# SpeakerStuff.net
KiCad netlist of a schematic drawn in EAGLE
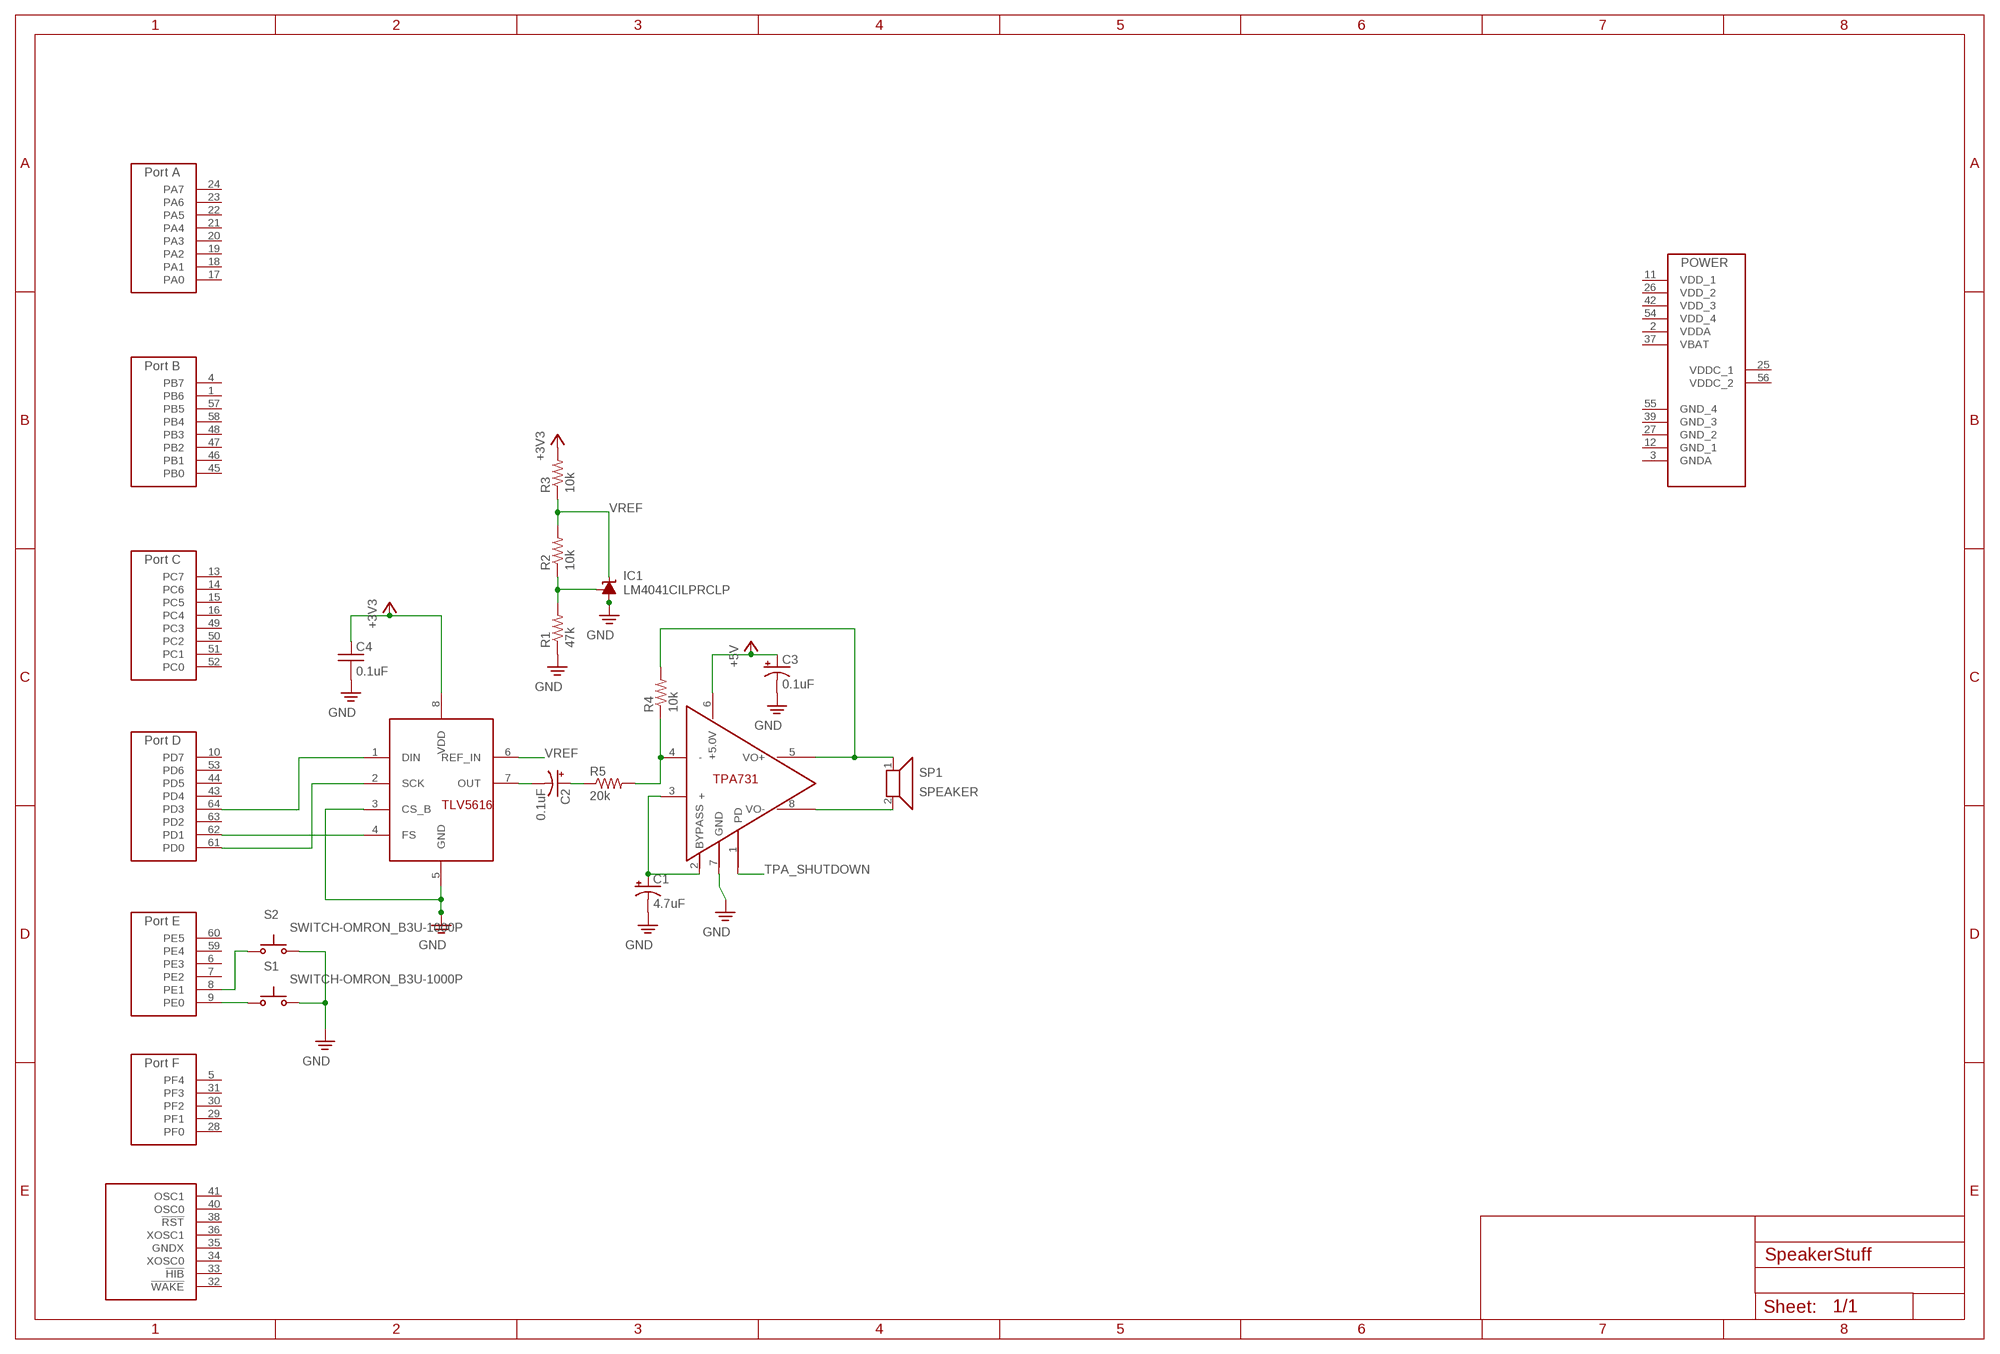
[diagram p0: schematic, sheet 1]

(export (version "E")
  (design (tool "Eeschema 10.0.6"))
  (components
    (comp (ref "C1")
      (value "4.7uF")
      (footprint "eagle-import:CAP200MILPOLARIZED")
      (libsource (lib "eagle-import") (part "CAPACITOR_POLARIZEDE5-6"))
    )
    (comp (ref "C2")
      (value "0.1uF")
      (footprint "eagle-import:CAP200MILPOLARIZED")
      (libsource (lib "eagle-import") (part "CAPACITOR_POLARIZEDE5-6"))
    )
    (comp (ref "C3")
      (value "0.1uF")
      (footprint "eagle-import:CAP200MILPOLARIZED")
      (libsource (lib "eagle-import") (part "CAPACITOR_POLARIZEDE5-6"))
    )
    (comp (ref "C4")
      (value "0.1uF")
      (footprint "eagle-import:C0603K")
      (libsource (lib "eagle-import") (part "CAPACITORC0603K"))
    )
    (comp (ref "IC1")
      (value "LM4041CILPRCLP")
      (footprint "eagle-import:LP_O-PBCY-W3")
      (fields (field (name "MPN") "LM4041CILP"))
      (libsource (lib "eagle-import") (part "LM4041CILPRLPC"))
    )
    (comp (ref "R1")
      (value "47k")
      (footprint "eagle-import:R0603")
      (libsource (lib "eagle-import") (part "RESISTORR0603"))
    )
    (comp (ref "R2")
      (value "10k")
      (footprint "eagle-import:R0603")
      (libsource (lib "eagle-import") (part "RESISTORR0603"))
    )
    (comp (ref "R3")
      (value "10k")
      (footprint "eagle-import:R0603")
      (libsource (lib "eagle-import") (part "RESISTORR0603"))
    )
    (comp (ref "R4")
      (value "10k")
      (footprint "eagle-import:R0603")
      (libsource (lib "eagle-import") (part "RESISTORR0603"))
    )
    (comp (ref "R5")
      (value "20k")
      (footprint "eagle-import:R0603")
      (libsource (lib "eagle-import") (part "RESISTORR0603"))
    )
    (comp (ref "S1")
      (value "SWITCH-OMRON_B3U-1000P")
      (footprint "eagle-import:SWITCH-OMRON_B3U-1000P")
      (libsource (lib "eagle-import") (part "SWITCH-OMRON_B3U-1000P"))
    )
    (comp (ref "S2")
      (value "SWITCH-OMRON_B3U-1000P")
      (footprint "eagle-import:SWITCH-OMRON_B3U-1000P")
      (libsource (lib "eagle-import") (part "SWITCH-OMRON_B3U-1000P"))
    )
    (comp (ref "SP1")
      (value "SPEAKER")
      (footprint "eagle-import:1X02")
      (libsource (lib "eagle-import") (part "SPEAKER"))
    )
    (comp (ref "U$1")
      (value "TM4C123GH6PM")
      (footprint "eagle-import:QFP50P1200X1200X160-64N")
      (libsource (lib "eagle-import") (part "TM4C123GH6PM"))
    )
    (comp (ref "U$2")
      (value "TM4C123GH6PM")
      (footprint "eagle-import:QFP50P1200X1200X160-64N")
      (libsource (lib "eagle-import") (part "TM4C123GH6PM"))
    )
    (comp (ref "U$3")
      (value "TM4C123GH6PM")
      (footprint "eagle-import:QFP50P1200X1200X160-64N")
      (libsource (lib "eagle-import") (part "TM4C123GH6PM"))
    )
    (comp (ref "U$4")
      (value "TM4C123GH6PM")
      (footprint "eagle-import:QFP50P1200X1200X160-64N")
      (libsource (lib "eagle-import") (part "TM4C123GH6PM"))
    )
    (comp (ref "U$5")
      (value "TM4C123GH6PM")
      (footprint "eagle-import:QFP50P1200X1200X160-64N")
      (libsource (lib "eagle-import") (part "TM4C123GH6PM"))
    )
    (comp (ref "U$6")
      (value "TM4C123GH6PM")
      (footprint "eagle-import:QFP50P1200X1200X160-64N")
      (libsource (lib "eagle-import") (part "TM4C123GH6PM"))
    )
    (comp (ref "U$7")
      (value "TM4C123GH6PM")
      (footprint "eagle-import:QFP50P1200X1200X160-64N")
      (libsource (lib "eagle-import") (part "TM4C123GH6PM"))
    )
    (comp (ref "U$8")
      (value "TM4C123GH6PM")
      (footprint "eagle-import:QFP50P1200X1200X160-64N")
      (libsource (lib "eagle-import") (part "TM4C123GH6PM"))
    )
    (comp (ref "U$9")
      (value "TLV5616")
      (footprint "eagle-import:DIL08")
      (libsource (lib "eagle-import") (part "TLV5616"))
    )
    (comp (ref "U$10")
      (value "TPA731")
      (footprint "eagle-import:SO08")
      (libsource (lib "eagle-import") (part "TPA731"))
    )
  )
  (nets
    (net (code "1") (name "+3V3") (class "Default")
      (node (ref "C4") (pin "1") (pinfunction "1_1") (pintype "passive"))
      (node (ref "R3") (pin "2") (pinfunction "2_2") (pintype "passive"))
      (node (ref "U$9") (pin "8") (pinfunction "VDD_8") (pintype "bidirectional"))
    )
    (net (code "2") (name "+5V") (class "Default")
      (node (ref "C3") (pin "+") (pinfunction "+_+") (pintype "passive"))
      (node (ref "U$10") (pin "6") (pinfunction "+5.0V_6") (pintype "bidirectional"))
    )
    (net (code "3") (name "/TPA_SHUTDOWN") (class "Default")
      (node (ref "U$10") (pin "1") (pinfunction "PD_1") (pintype "bidirectional"))
    )
    (net (code "4") (name "/VREF") (class "Default")
      (node (ref "IC1") (pin "2") (pinfunction "C_2") (pintype "passive"))
      (node (ref "R2") (pin "2") (pinfunction "2_2") (pintype "passive"))
      (node (ref "R3") (pin "1") (pinfunction "1_1") (pintype "passive"))
      (node (ref "U$9") (pin "6") (pinfunction "REF_IN_6") (pintype "bidirectional"))
    )
    (net (code "5") (name "GND") (class "Default")
      (node (ref "C1") (pin "-") (pinfunction "-_-") (pintype "passive"))
      (node (ref "C3") (pin "-") (pinfunction "-_-") (pintype "passive"))
      (node (ref "C4") (pin "2") (pinfunction "2_2") (pintype "passive"))
      (node (ref "IC1") (pin "3") (pinfunction "A_3") (pintype "passive"))
      (node (ref "R1") (pin "1") (pinfunction "1_1") (pintype "passive"))
      (node (ref "S1") (pin "2") (pinfunction "S_2") (pintype "passive"))
      (node (ref "S2") (pin "2") (pinfunction "S_2") (pintype "passive"))
      (node (ref "U$10") (pin "7") (pinfunction "GND_7") (pintype "bidirectional"))
      (node (ref "U$9") (pin "3") (pinfunction "CS_B_3") (pintype "bidirectional"))
      (node (ref "U$9") (pin "5") (pinfunction "GND_5") (pintype "bidirectional"))
    )
    (net (code "6") (name "Net-(C2-Pad+)") (class "Default")
      (node (ref "C2") (pin "+") (pinfunction "+_+") (pintype "passive"))
      (node (ref "R5") (pin "1") (pinfunction "1_1") (pintype "passive"))
    )
    (net (code "7") (name "Net-(IC1-FB)") (class "Default")
      (node (ref "IC1") (pin "1") (pinfunction "FB_1") (pintype "passive"))
      (node (ref "R1") (pin "2") (pinfunction "2_2") (pintype "passive"))
      (node (ref "R2") (pin "1") (pinfunction "1_1") (pintype "passive"))
    )
    (net (code "8") (name "Net-(S1-P)") (class "Default")
      (node (ref "S1") (pin "1") (pinfunction "P_1") (pintype "passive"))
      (node (ref "U$6") (pin "9") (pinfunction "PE0_9") (pintype "bidirectional"))
    )
    (net (code "9") (name "Net-(S2-P)") (class "Default")
      (node (ref "S2") (pin "1") (pinfunction "P_1") (pintype "passive"))
      (node (ref "U$6") (pin "8") (pinfunction "PE1_8") (pintype "bidirectional"))
    )
    (net (code "10") (name "Net-(U$5D-PD0)") (class "Default")
      (node (ref "U$5") (pin "61") (pinfunction "PD0_61") (pintype "bidirectional"))
      (node (ref "U$9") (pin "2") (pinfunction "SCK_2") (pintype "bidirectional"))
    )
    (net (code "11") (name "Net-(U$5D-PD1)") (class "Default")
      (node (ref "U$5") (pin "62") (pinfunction "PD1_62") (pintype "bidirectional"))
      (node (ref "U$9") (pin "4") (pinfunction "FS_4") (pintype "bidirectional"))
    )
    (net (code "12") (name "Net-(U$5D-PD3)") (class "Default")
      (node (ref "U$5") (pin "64") (pinfunction "PD3_64") (pintype "bidirectional"))
      (node (ref "U$9") (pin "1") (pinfunction "DIN_1") (pintype "bidirectional"))
    )
    (net (code "13") (name "Net-(U$9-OUT)") (class "Default")
      (node (ref "C2") (pin "-") (pinfunction "-_-") (pintype "passive"))
      (node (ref "U$9") (pin "7") (pinfunction "OUT_7") (pintype "bidirectional"))
    )
    (net (code "14") (name "Net-(U$10-+)") (class "Default")
      (node (ref "C1") (pin "+") (pinfunction "+_+") (pintype "passive"))
      (node (ref "U$10") (pin "2") (pinfunction "BYPASS_2") (pintype "bidirectional"))
      (node (ref "U$10") (pin "3") (pinfunction "+_3") (pintype "bidirectional"))
    )
    (net (code "15") (name "Net-(U$10--)") (class "Default")
      (node (ref "R4") (pin "1") (pinfunction "1_1") (pintype "passive"))
      (node (ref "R5") (pin "2") (pinfunction "2_2") (pintype "passive"))
      (node (ref "U$10") (pin "4") (pinfunction "-_4") (pintype "bidirectional"))
    )
    (net (code "16") (name "Net-(U$10-VO+)") (class "Default")
      (node (ref "R4") (pin "2") (pinfunction "2_2") (pintype "passive"))
      (node (ref "SP1") (pin "1") (pinfunction "1_1") (pintype "passive"))
      (node (ref "U$10") (pin "5") (pinfunction "VO+_5") (pintype "bidirectional"))
    )
    (net (code "17") (name "Net-(U$10-VO-)") (class "Default")
      (node (ref "SP1") (pin "2") (pinfunction "2_2") (pintype "passive"))
      (node (ref "U$10") (pin "8") (pinfunction "VO-_8") (pintype "bidirectional"))
    )
    (net (code "18") (name "unconnected-(U$1G-GNDX-Pad35)") (class "Default")
      (node (ref "U$1") (pin "35") (pinfunction "GNDX_35") (pintype "bidirectional"))
    )
    (net (code "19") (name "unconnected-(U$1G-OSC0-Pad40)") (class "Default")
      (node (ref "U$1") (pin "40") (pinfunction "OSC0_40") (pintype "bidirectional"))
    )
    (net (code "20") (name "unconnected-(U$1G-OSC1-Pad41)") (class "Default")
      (node (ref "U$1") (pin "41") (pinfunction "OSC1_41") (pintype "bidirectional"))
    )
    (net (code "21") (name "unconnected-(U$1G-XOSC0-Pad34)") (class "Default")
      (node (ref "U$1") (pin "34") (pinfunction "XOSC0_34") (pintype "bidirectional"))
    )
    (net (code "22") (name "unconnected-(U$1G-XOSC1-Pad36)") (class "Default")
      (node (ref "U$1") (pin "36") (pinfunction "XOSC1_36") (pintype "bidirectional"))
    )
    (net (code "23") (name "unconnected-(U$1G-~{HIB}-Pad33)") (class "Default")
      (node (ref "U$1") (pin "33") (pinfunction "~{HIB}_33") (pintype "bidirectional"))
    )
    (net (code "24") (name "unconnected-(U$1G-~{RST}-Pad38)") (class "Default")
      (node (ref "U$1") (pin "38") (pinfunction "~{RST}_38") (pintype "bidirectional"))
    )
    (net (code "25") (name "unconnected-(U$1G-~{WAKE}-Pad32)") (class "Default")
      (node (ref "U$1") (pin "32") (pinfunction "~{WAKE}_32") (pintype "bidirectional"))
    )
    (net (code "26") (name "unconnected-(U$2A-PA0-Pad17)") (class "Default")
      (node (ref "U$2") (pin "17") (pinfunction "PA0_17") (pintype "bidirectional"))
    )
    (net (code "27") (name "unconnected-(U$2A-PA1-Pad18)") (class "Default")
      (node (ref "U$2") (pin "18") (pinfunction "PA1_18") (pintype "bidirectional"))
    )
    (net (code "28") (name "unconnected-(U$2A-PA2-Pad19)") (class "Default")
      (node (ref "U$2") (pin "19") (pinfunction "PA2_19") (pintype "bidirectional"))
    )
    (net (code "29") (name "unconnected-(U$2A-PA3-Pad20)") (class "Default")
      (node (ref "U$2") (pin "20") (pinfunction "PA3_20") (pintype "bidirectional"))
    )
    (net (code "30") (name "unconnected-(U$2A-PA4-Pad21)") (class "Default")
      (node (ref "U$2") (pin "21") (pinfunction "PA4_21") (pintype "bidirectional"))
    )
    (net (code "31") (name "unconnected-(U$2A-PA5-Pad22)") (class "Default")
      (node (ref "U$2") (pin "22") (pinfunction "PA5_22") (pintype "bidirectional"))
    )
    (net (code "32") (name "unconnected-(U$2A-PA6-Pad23)") (class "Default")
      (node (ref "U$2") (pin "23") (pinfunction "PA6_23") (pintype "bidirectional"))
    )
    (net (code "33") (name "unconnected-(U$2A-PA7-Pad24)") (class "Default")
      (node (ref "U$2") (pin "24") (pinfunction "PA7_24") (pintype "bidirectional"))
    )
    (net (code "34") (name "unconnected-(U$3B-PB0-Pad45)") (class "Default")
      (node (ref "U$3") (pin "45") (pinfunction "PB0_45") (pintype "bidirectional"))
    )
    (net (code "35") (name "unconnected-(U$3B-PB1-Pad46)") (class "Default")
      (node (ref "U$3") (pin "46") (pinfunction "PB1_46") (pintype "bidirectional"))
    )
    (net (code "36") (name "unconnected-(U$3B-PB2-Pad47)") (class "Default")
      (node (ref "U$3") (pin "47") (pinfunction "PB2_47") (pintype "bidirectional"))
    )
    (net (code "37") (name "unconnected-(U$3B-PB3-Pad48)") (class "Default")
      (node (ref "U$3") (pin "48") (pinfunction "PB3_48") (pintype "bidirectional"))
    )
    (net (code "38") (name "unconnected-(U$3B-PB4-Pad58)") (class "Default")
      (node (ref "U$3") (pin "58") (pinfunction "PB4_58") (pintype "bidirectional"))
    )
    (net (code "39") (name "unconnected-(U$3B-PB5-Pad57)") (class "Default")
      (node (ref "U$3") (pin "57") (pinfunction "PB5_57") (pintype "bidirectional"))
    )
    (net (code "40") (name "unconnected-(U$3B-PB6-Pad1)") (class "Default")
      (node (ref "U$3") (pin "1") (pinfunction "PB6_1") (pintype "bidirectional"))
    )
    (net (code "41") (name "unconnected-(U$3B-PB7-Pad4)") (class "Default")
      (node (ref "U$3") (pin "4") (pinfunction "PB7_4") (pintype "bidirectional"))
    )
    (net (code "42") (name "unconnected-(U$4C-PC0-Pad52)") (class "Default")
      (node (ref "U$4") (pin "52") (pinfunction "PC0_52") (pintype "bidirectional"))
    )
    (net (code "43") (name "unconnected-(U$4C-PC1-Pad51)") (class "Default")
      (node (ref "U$4") (pin "51") (pinfunction "PC1_51") (pintype "bidirectional"))
    )
    (net (code "44") (name "unconnected-(U$4C-PC2-Pad50)") (class "Default")
      (node (ref "U$4") (pin "50") (pinfunction "PC2_50") (pintype "bidirectional"))
    )
    (net (code "45") (name "unconnected-(U$4C-PC3-Pad49)") (class "Default")
      (node (ref "U$4") (pin "49") (pinfunction "PC3_49") (pintype "bidirectional"))
    )
    (net (code "46") (name "unconnected-(U$4C-PC4-Pad16)") (class "Default")
      (node (ref "U$4") (pin "16") (pinfunction "PC4_16") (pintype "bidirectional"))
    )
    (net (code "47") (name "unconnected-(U$4C-PC5-Pad15)") (class "Default")
      (node (ref "U$4") (pin "15") (pinfunction "PC5_15") (pintype "bidirectional"))
    )
    (net (code "48") (name "unconnected-(U$4C-PC6-Pad14)") (class "Default")
      (node (ref "U$4") (pin "14") (pinfunction "PC6_14") (pintype "bidirectional"))
    )
    (net (code "49") (name "unconnected-(U$4C-PC7-Pad13)") (class "Default")
      (node (ref "U$4") (pin "13") (pinfunction "PC7_13") (pintype "bidirectional"))
    )
    (net (code "50") (name "unconnected-(U$5D-PD2-Pad63)") (class "Default")
      (node (ref "U$5") (pin "63") (pinfunction "PD2_63") (pintype "bidirectional"))
    )
    (net (code "51") (name "unconnected-(U$5D-PD4-Pad43)") (class "Default")
      (node (ref "U$5") (pin "43") (pinfunction "PD4_43") (pintype "bidirectional"))
    )
    (net (code "52") (name "unconnected-(U$5D-PD5-Pad44)") (class "Default")
      (node (ref "U$5") (pin "44") (pinfunction "PD5_44") (pintype "bidirectional"))
    )
    (net (code "53") (name "unconnected-(U$5D-PD6-Pad53)") (class "Default")
      (node (ref "U$5") (pin "53") (pinfunction "PD6_53") (pintype "bidirectional"))
    )
    (net (code "54") (name "unconnected-(U$5D-PD7-Pad10)") (class "Default")
      (node (ref "U$5") (pin "10") (pinfunction "PD7_10") (pintype "bidirectional"))
    )
    (net (code "55") (name "unconnected-(U$6E-PE2-Pad7)") (class "Default")
      (node (ref "U$6") (pin "7") (pinfunction "PE2_7") (pintype "bidirectional"))
    )
    (net (code "56") (name "unconnected-(U$6E-PE3-Pad6)") (class "Default")
      (node (ref "U$6") (pin "6") (pinfunction "PE3_6") (pintype "bidirectional"))
    )
    (net (code "57") (name "unconnected-(U$6E-PE4-Pad59)") (class "Default")
      (node (ref "U$6") (pin "59") (pinfunction "PE4_59") (pintype "bidirectional"))
    )
    (net (code "58") (name "unconnected-(U$6E-PE5-Pad60)") (class "Default")
      (node (ref "U$6") (pin "60") (pinfunction "PE5_60") (pintype "bidirectional"))
    )
    (net (code "59") (name "unconnected-(U$7F-PF0-Pad28)") (class "Default")
      (node (ref "U$7") (pin "28") (pinfunction "PF0_28") (pintype "bidirectional"))
    )
    (net (code "60") (name "unconnected-(U$7F-PF1-Pad29)") (class "Default")
      (node (ref "U$7") (pin "29") (pinfunction "PF1_29") (pintype "bidirectional"))
    )
    (net (code "61") (name "unconnected-(U$7F-PF2-Pad30)") (class "Default")
      (node (ref "U$7") (pin "30") (pinfunction "PF2_30") (pintype "bidirectional"))
    )
    (net (code "62") (name "unconnected-(U$7F-PF3-Pad31)") (class "Default")
      (node (ref "U$7") (pin "31") (pinfunction "PF3_31") (pintype "bidirectional"))
    )
    (net (code "63") (name "unconnected-(U$7F-PF4-Pad5)") (class "Default")
      (node (ref "U$7") (pin "5") (pinfunction "PF4_5") (pintype "bidirectional"))
    )
    (net (code "64") (name "unconnected-(U$8H-GNDA-Pad3)") (class "Default")
      (node (ref "U$8") (pin "3") (pinfunction "GNDA_3") (pintype "bidirectional"))
    )
    (net (code "65") (name "unconnected-(U$8H-GND_1-Pad12)") (class "Default")
      (node (ref "U$8") (pin "12") (pinfunction "GND_1_12") (pintype "bidirectional"))
    )
    (net (code "66") (name "unconnected-(U$8H-GND_2-Pad27)") (class "Default")
      (node (ref "U$8") (pin "27") (pinfunction "GND_2_27") (pintype "bidirectional"))
    )
    (net (code "67") (name "unconnected-(U$8H-GND_3-Pad39)") (class "Default")
      (node (ref "U$8") (pin "39") (pinfunction "GND_3_39") (pintype "bidirectional"))
    )
    (net (code "68") (name "unconnected-(U$8H-GND_4-Pad55)") (class "Default")
      (node (ref "U$8") (pin "55") (pinfunction "GND_4_55") (pintype "bidirectional"))
    )
    (net (code "69") (name "unconnected-(U$8H-VBAT-Pad37)") (class "Default")
      (node (ref "U$8") (pin "37") (pinfunction "VBAT_37") (pintype "bidirectional"))
    )
    (net (code "70") (name "unconnected-(U$8H-VDDA-Pad2)") (class "Default")
      (node (ref "U$8") (pin "2") (pinfunction "VDDA_2") (pintype "bidirectional"))
    )
    (net (code "71") (name "unconnected-(U$8H-VDDC_1-Pad25)") (class "Default")
      (node (ref "U$8") (pin "25") (pinfunction "VDDC_1_25") (pintype "bidirectional"))
    )
    (net (code "72") (name "unconnected-(U$8H-VDDC_2-Pad56)") (class "Default")
      (node (ref "U$8") (pin "56") (pinfunction "VDDC_2_56") (pintype "bidirectional"))
    )
    (net (code "73") (name "unconnected-(U$8H-VDD_1-Pad11)") (class "Default")
      (node (ref "U$8") (pin "11") (pinfunction "VDD_1_11") (pintype "bidirectional"))
    )
    (net (code "74") (name "unconnected-(U$8H-VDD_2-Pad26)") (class "Default")
      (node (ref "U$8") (pin "26") (pinfunction "VDD_2_26") (pintype "bidirectional"))
    )
    (net (code "75") (name "unconnected-(U$8H-VDD_3-Pad42)") (class "Default")
      (node (ref "U$8") (pin "42") (pinfunction "VDD_3_42") (pintype "bidirectional"))
    )
    (net (code "76") (name "unconnected-(U$8H-VDD_4-Pad54)") (class "Default")
      (node (ref "U$8") (pin "54") (pinfunction "VDD_4_54") (pintype "bidirectional"))
    )
  )
)
